# Super-Regenerative-FM.net
KiCad netlist of a schematic drawn in EAGLE
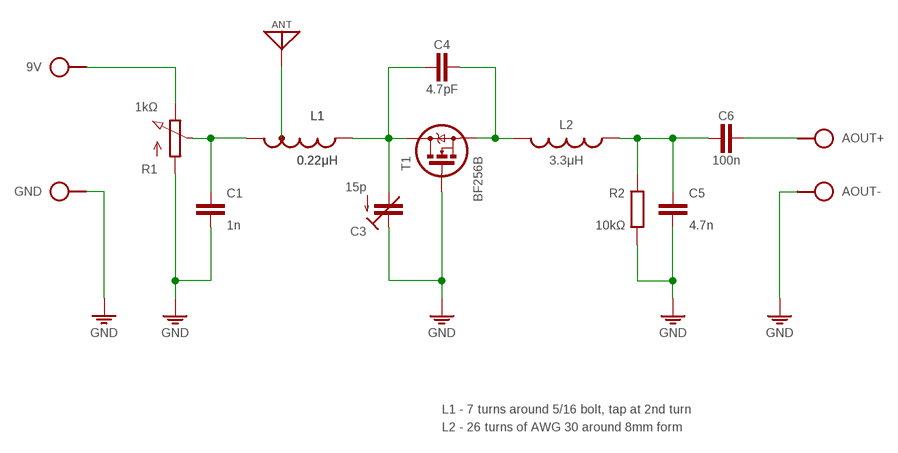
[diagram p0: schematic, sheet 1]

(export (version "E")
  (design (tool "Eeschema 10.0.6"))
  (components
    (comp (ref "9V")
      (value "SPAD")
      (footprint "eagle-import:SPAD")
      (libsource (lib "eagle-import") (part "SPAD"))
    )
    (comp (ref "ANT")
      (value "ANT")
      (footprint "eagle-import:SPAD")
      (libsource (lib "eagle-import") (part "ANT"))
    )
    (comp (ref "AOUT+")
      (value "SPAD")
      (footprint "eagle-import:SPAD")
      (libsource (lib "eagle-import") (part "SPAD"))
    )
    (comp (ref "AOUT-")
      (value "SPAD")
      (footprint "eagle-import:SPAD")
      (libsource (lib "eagle-import") (part "SPAD"))
    )
    (comp (ref "C1")
      (value "1n")
      (footprint "eagle-import:C050-020X036_V")
      (libsource (lib "eagle-import") (part "C050-020X036/V"))
    )
    (comp (ref "C3")
      (value "15p")
      (footprint "eagle-import:TRIM-2222-808")
      (libsource (lib "eagle-import") (part "C-TR-PH201272222-808-2PIN"))
    )
    (comp (ref "C4")
      (value "4.7pF")
      (footprint "eagle-import:C050-020X036")
      (libsource (lib "eagle-import") (part "C050-020X036"))
    )
    (comp (ref "C5")
      (value "4.7n")
      (footprint "eagle-import:C050-020X044")
      (libsource (lib "eagle-import") (part "C050-020X044"))
    )
    (comp (ref "C6")
      (value "100n")
      (footprint "eagle-import:C050-020X044")
      (libsource (lib "eagle-import") (part "C050-020X044"))
    )
    (comp (ref "GND")
      (value "SPAD")
      (footprint "eagle-import:SPAD")
      (libsource (lib "eagle-import") (part "SPAD"))
    )
    (comp (ref "L1")
      (value "0.22μH")
      (footprint "eagle-import:L-08_12-X-TAP1")
      (libsource (lib "eagle-import") (part "L-TAP1L-08/12-X-TAP1"))
    )
    (comp (ref "L2")
      (value "3.3μH")
      (footprint "eagle-import:L-BODY")
      (libsource (lib "eagle-import") (part "L-BODY"))
    )
    (comp (ref "R1")
      (value "1kΩ")
      (footprint "eagle-import:POT-V")
      (libsource (lib "eagle-import") (part "POT-V"))
    )
    (comp (ref "R2")
      (value "10kΩ")
      (footprint "eagle-import:0204_10")
      (libsource (lib "eagle-import") (part "R0204/10"))
    )
    (comp (ref "T1")
      (value "BF256B")
      (footprint "eagle-import:TO92")
      (libsource (lib "eagle-import") (part "BF256B"))
    )
  )
  (nets
    (net (code "1") (name "GND") (class "Default")
      (node (ref "AOUT-") (pin "1") (pinfunction "P$1_1") (pintype "bidirectional"))
      (node (ref "C1") (pin "2") (pinfunction "2_2") (pintype "passive"))
      (node (ref "C3") (pin "1") (pinfunction "E_1") (pintype "passive"))
      (node (ref "C5") (pin "2") (pinfunction "2_2") (pintype "passive"))
      (node (ref "GND") (pin "1") (pinfunction "P$1_1") (pintype "bidirectional"))
      (node (ref "R1") (pin "A") (pinfunction "A_A") (pintype "passive"))
      (node (ref "R2") (pin "1") (pinfunction "1_1") (pintype "passive"))
      (node (ref "T1") (pin "1") (pinfunction "G_1") (pintype "passive"))
    )
    (net (code "2") (name "Net-(9V-P$1)") (class "Default")
      (node (ref "9V") (pin "1") (pinfunction "P$1_1") (pintype "bidirectional"))
      (node (ref "R1") (pin "E") (pinfunction "E_E") (pintype "passive"))
    )
    (net (code "3") (name "Net-(AOUT+-P$1)") (class "Default")
      (node (ref "AOUT+") (pin "1") (pinfunction "P$1_1") (pintype "bidirectional"))
      (node (ref "C6") (pin "2") (pinfunction "2_2") (pintype "passive"))
    )
    (net (code "4") (name "Net-(C1-Pad1)") (class "Default")
      (node (ref "C1") (pin "1") (pinfunction "1_1") (pintype "passive"))
      (node (ref "L1") (pin "1") (pinfunction "1_1") (pintype "passive"))
      (node (ref "R1") (pin "S") (pinfunction "S_S") (pintype "passive"))
    )
    (net (code "5") (name "Net-(C3-A)") (class "Default")
      (node (ref "C3") (pin "2") (pinfunction "A_2") (pintype "passive"))
      (node (ref "C4") (pin "1") (pinfunction "1_1") (pintype "passive"))
      (node (ref "L1") (pin "2") (pinfunction "2_2") (pintype "passive"))
      (node (ref "T1") (pin "3") (pinfunction "D_3") (pintype "passive"))
    )
    (net (code "6") (name "Net-(L1-T)") (class "Default")
      (node (ref "ANT") (pin "1") (pinfunction "1_1") (pintype "output"))
      (node (ref "L1") (pin "3") (pinfunction "T_3") (pintype "passive"))
    )
    (net (code "7") (name "Net-(L2-1)") (class "Default")
      (node (ref "C5") (pin "1") (pinfunction "1_1") (pintype "passive"))
      (node (ref "C6") (pin "1") (pinfunction "1_1") (pintype "passive"))
      (node (ref "L2") (pin "2") (pinfunction "1_2") (pintype "passive"))
      (node (ref "R2") (pin "2") (pinfunction "2_2") (pintype "passive"))
    )
    (net (code "8") (name "Net-(L2-2)") (class "Default")
      (node (ref "C4") (pin "2") (pinfunction "2_2") (pintype "passive"))
      (node (ref "L2") (pin "3") (pinfunction "2_3") (pintype "passive"))
      (node (ref "T1") (pin "2") (pinfunction "S_2") (pintype "passive"))
    )
  )
)
